# Port.net
KiCad netlist of a schematic drawn in Altium Designer
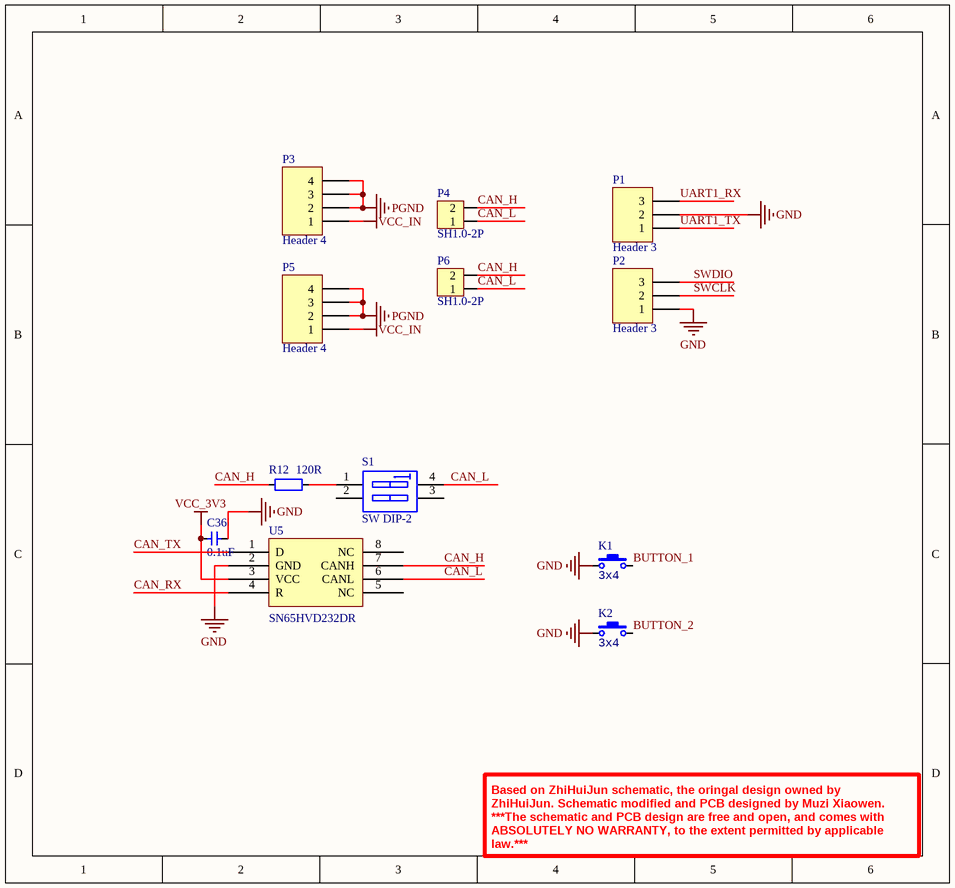
[diagram p0: Port.SchDoc]

(export (version "E")
  (design (tool "Eeschema 10.0.6"))
  (components
    (comp (ref "C36")
      (value "0.1uF")
      (footprint "motor42-lib:CAP_0402")
      (description "Capacitor")
      (libsource (lib "MyPcbLib") (part "电容-0402"))
    )
    (comp (ref "K1")
      (value "3x4")
      (footprint "ButtonTACT_3x4x2_180")
      (description "Button")
      (fields (field (name "Comment") "TACT 2P"))
      (libsource (lib "KitSprout") (part "ButtonTACT_3x4x2_180"))
    )
    (comp (ref "K2")
      (value "3x4")
      (footprint "ButtonTACT_3x4x2_180")
      (description "Button")
      (fields (field (name "Comment") "TACT 2P"))
      (libsource (lib "KitSprout") (part "ButtonTACT_3x4x2_180"))
    )
    (comp (ref "P1")
      (value "Header 3")
      (footprint "HDR1X3")
      (description "Header, 3-Pin")
      (fields (field (name "PUBLISHER") "Altium Limited"))
      (libsource (lib "Miscellaneous Connectors") (part "Header 3"))
    )
    (comp (ref "P2")
      (value "Header 3")
      (footprint "HDR1X3")
      (description "Header, 3-Pin")
      (fields (field (name "PUBLISHER") "Altium Limited"))
      (libsource (lib "Miscellaneous Connectors") (part "Header 3"))
    )
    (comp (ref "P3")
      (value "Header 4")
      (footprint "CONN-SMD_2P-P2.00_HDGC_HDGC2001WR-S-2P")
      (description "Header, 4-Pin")
      (fields (field (name "PUBLISHER") "Altium Limited"))
      (libsource (lib "Miscellaneous Connectors") (part "Header 4"))
    )
    (comp (ref "P4") (value "SH1.0-2P") (footprint "SH1.0-2P") (libsource (lib "MyPcbLib") (part "SH1.0-2P")))
    (comp (ref "P5")
      (value "Header 4")
      (footprint "CONN-SMD_2P-P2.00_HDGC_HDGC2001WR-S-2P")
      (description "Header, 4-Pin")
      (fields (field (name "PUBLISHER") "Altium Limited"))
      (libsource (lib "Miscellaneous Connectors") (part "Header 4"))
    )
    (comp (ref "P6") (value "SH1.0-2P") (footprint "SH1.0-2P") (libsource (lib "MyPcbLib") (part "SH1.0-2P")))
    (comp (ref "R12")
      (value "120R")
      (footprint "RES_0402")
      (description "Resistor")
      (libsource (lib "MyPcbLib") (part "电阻-0402"))
    )
    (comp (ref "S1")
      (value "SW DIP-2")
      (footprint "SW-SMD_DSHP02TS-S")
      (description "DIP Switch, 2 Position, SPST")
      (fields (field (name "PUBLISHER") "Altium Limited"))
      (libsource (lib "Miscellaneous Devices") (part "SW DIP-2"))
    )
    (comp (ref "U5")
      (value "SN65HVD232D")
      (footprint "so-8")
      (fields
        (field (name "MANUFACTURER") "Texas Instruments")
        (field (name "MANUFACTURER PART NUMBER") "SN65HVD232DR")
      )
      (libsource (lib "MyPcbLib") (part "SN65HVD232D"))
    )
  )
  (nets
    (net (code "1") (name "/BUTTON_1") (class "Default")
      (node (ref "K1") (pin "2") (pinfunction "2_2") (pintype "passive"))
    )
    (net (code "2") (name "/BUTTON_2") (class "Default")
      (node (ref "K2") (pin "2") (pinfunction "2_2") (pintype "passive"))
    )
    (net (code "3") (name "/CAN_H") (class "Default")
      (node (ref "P4") (pin "2") (pinfunction "2_2") (pintype "passive"))
      (node (ref "P6") (pin "2") (pinfunction "2_2") (pintype "passive"))
      (node (ref "R12") (pin "1") (pinfunction "1_1") (pintype "passive"))
      (node (ref "U5") (pin "7") (pinfunction "CANH_7") (pintype "passive"))
    )
    (net (code "4") (name "/CAN_L") (class "Default")
      (node (ref "P4") (pin "1") (pinfunction "1_1") (pintype "passive"))
      (node (ref "P6") (pin "1") (pinfunction "1_1") (pintype "passive"))
      (node (ref "S1") (pin "4") (pinfunction "B1_4") (pintype "passive"))
      (node (ref "U5") (pin "6") (pinfunction "CANL_6") (pintype "passive"))
    )
    (net (code "5") (name "/CAN_RX") (class "Default")
      (node (ref "U5") (pin "4") (pinfunction "R_4") (pintype "passive"))
    )
    (net (code "6") (name "/CAN_TX") (class "Default")
      (node (ref "U5") (pin "1") (pinfunction "D_1") (pintype "passive"))
    )
    (net (code "7") (name "/SWCLK") (class "Default")
      (node (ref "P2") (pin "2") (pinfunction "2_2") (pintype "passive"))
    )
    (net (code "8") (name "/SWDIO") (class "Default")
      (node (ref "P2") (pin "3") (pinfunction "3_3") (pintype "passive"))
    )
    (net (code "9") (name "/UART1_RX") (class "Default")
      (node (ref "P1") (pin "3") (pinfunction "3_3") (pintype "passive"))
    )
    (net (code "10") (name "/UART1_TX") (class "Default")
      (node (ref "P1") (pin "1") (pinfunction "1_1") (pintype "passive"))
    )
    (net (code "11") (name "GND") (class "Default")
      (node (ref "C36") (pin "1") (pinfunction "1_1") (pintype "passive"))
      (node (ref "K1") (pin "1") (pinfunction "1_1") (pintype "passive"))
      (node (ref "K2") (pin "1") (pinfunction "1_1") (pintype "passive"))
      (node (ref "P1") (pin "2") (pinfunction "2_2") (pintype "passive"))
      (node (ref "P2") (pin "1") (pinfunction "1_1") (pintype "passive"))
      (node (ref "U5") (pin "2") (pinfunction "GND_2") (pintype "passive"))
    )
    (net (code "12") (name "Net-(S1-A1)") (class "Default")
      (node (ref "R12") (pin "2") (pinfunction "2_2") (pintype "passive"))
      (node (ref "S1") (pin "1") (pinfunction "A1_1") (pintype "passive"))
    )
    (net (code "13") (name "PGND") (class "Default")
      (node (ref "P3") (pin "2") (pinfunction "2_2") (pintype "passive"))
      (node (ref "P3") (pin "3") (pinfunction "3_3") (pintype "passive"))
      (node (ref "P3") (pin "4") (pinfunction "4_4") (pintype "passive"))
      (node (ref "P5") (pin "2") (pinfunction "2_2") (pintype "passive"))
      (node (ref "P5") (pin "3") (pinfunction "3_3") (pintype "passive"))
      (node (ref "P5") (pin "4") (pinfunction "4_4") (pintype "passive"))
    )
    (net (code "14") (name "VCC_3V3") (class "Default")
      (node (ref "C36") (pin "2") (pinfunction "2_2") (pintype "passive"))
      (node (ref "U5") (pin "3") (pinfunction "VCC_3") (pintype "passive"))
    )
    (net (code "15") (name "VCC_IN") (class "Default")
      (node (ref "P3") (pin "1") (pinfunction "1_1") (pintype "passive"))
      (node (ref "P5") (pin "1") (pinfunction "1_1") (pintype "passive"))
    )
    (net (code "16") (name "unconnected-(S1-A2-Pad2)") (class "Default")
      (node (ref "S1") (pin "2") (pinfunction "A2_2") (pintype "passive"))
    )
    (net (code "17") (name "unconnected-(S1-B2-Pad3)") (class "Default")
      (node (ref "S1") (pin "3") (pinfunction "B2_3") (pintype "passive"))
    )
    (net (code "18") (name "unconnected-(U5-NC-Pad5)") (class "Default")
      (node (ref "U5") (pin "5") (pinfunction "NC_5") (pintype "passive"))
    )
    (net (code "19") (name "unconnected-(U5-NC-Pad8)") (class "Default")
      (node (ref "U5") (pin "8") (pinfunction "NC_8") (pintype "passive"))
    )
  )
)
